# Motor.net
KiCad netlist of a schematic drawn in Altium Designer
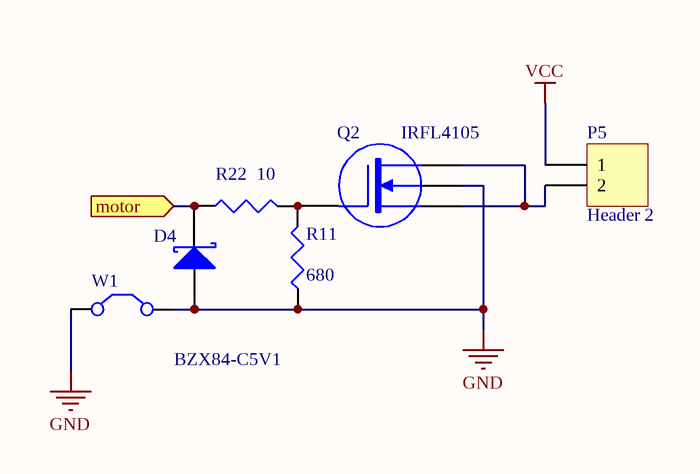
[diagram p0: Motor.SchDoc]

(export (version "E")
  (design (tool "Eeschema 10.0.6"))
  (components
    (comp (ref "D4")
      (value "BZX84-C5V1")
      (footprint "SOT-23_N")
      (description "Silicon AF Schottky Diode for High-Speed Switching")
      (fields (field (name "PUBLISHER") "Altium Limited"))
      (libsource (lib "Miscellaneous Devices") (part "Diode BAS70"))
    )
    (comp (ref "P5")
      (value "Header 2")
      (footprint "HDR1X2")
      (description "Header, 2-Pin")
      (fields (field (name "PUBLISHER") "Altium Limited"))
      (libsource (lib "Miscellaneous Connectors") (part "Header 2"))
    )
    (comp (ref "Q2")
      (value "IRFL4105")
      (footprint "Miscellaneous Devices:sot223_l")
      (description "N-Channel MOSFET, Externally Terminated Substrate")
      (fields (field (name "PUBLISHER") "Altium Limited"))
      (libsource (lib "IRFL4105") (part "MOSFET-N4"))
    )
    (comp (ref "R11")
      (value "680")
      (footprint "J1-0603")
      (description "Resistor")
      (fields (field (name "Comment") "Res3") (field (name "PUBLISHER") "Altium Limited"))
      (libsource (lib "Miscellaneous Devices") (part "Res3"))
    )
    (comp (ref "R22")
      (value "10")
      (footprint "J1-0603")
      (description "Resistor")
      (fields (field (name "Comment") "Res3") (field (name "PUBLISHER") "Altium Limited"))
      (libsource (lib "Miscellaneous Devices") (part "Res3"))
    )
    (comp (ref "W1")
      (value "Jumper")
      (footprint "JAMP:PCBComponent_1")
      (description "Jumper Wire")
      (fields (field (name "PUBLISHER") "Altium Limited"))
      (libsource (lib "JAMP") (part "Jumper"))
    )
  )
  (nets
    (net (code "1") (name "/motor") (class "Default")
      (node (ref "D4") (pin "3") (pinfunction "K_3") (pintype "passive"))
      (node (ref "R22") (pin "1") (pinfunction "1_1") (pintype "passive"))
    )
    (net (code "2") (name "GND") (class "Default")
      (node (ref "D4") (pin "1") (pinfunction "A_1") (pintype "passive"))
      (node (ref "Q2") (pin "3") (pinfunction "U_3") (pintype "passive"))
      (node (ref "R11") (pin "1") (pinfunction "1_1") (pintype "passive"))
      (node (ref "W1") (pin "1") (pinfunction "C1_1") (pintype "passive"))
      (node (ref "W1") (pin "2") (pinfunction "C2_2") (pintype "passive"))
    )
    (net (code "3") (name "Net-(Q2-D)") (class "Default")
      (node (ref "P5") (pin "2") (pinfunction "2_2") (pintype "passive"))
      (node (ref "Q2") (pin "2") (pinfunction "D_2") (pintype "passive"))
      (node (ref "Q2") (pin "4") (pinfunction "S_4") (pintype "passive"))
    )
    (net (code "4") (name "Net-(Q2-G)") (class "Default")
      (node (ref "Q2") (pin "1") (pinfunction "G_1") (pintype "passive"))
      (node (ref "R11") (pin "2") (pinfunction "2_2") (pintype "passive"))
      (node (ref "R22") (pin "2") (pinfunction "2_2") (pintype "passive"))
    )
    (net (code "5") (name "VCC") (class "Default")
      (node (ref "P5") (pin "1") (pinfunction "1_1") (pintype "passive"))
    )
  )
)
